# DriversBoard.net
KiCad netlist of a schematic drawn in Altium Designer
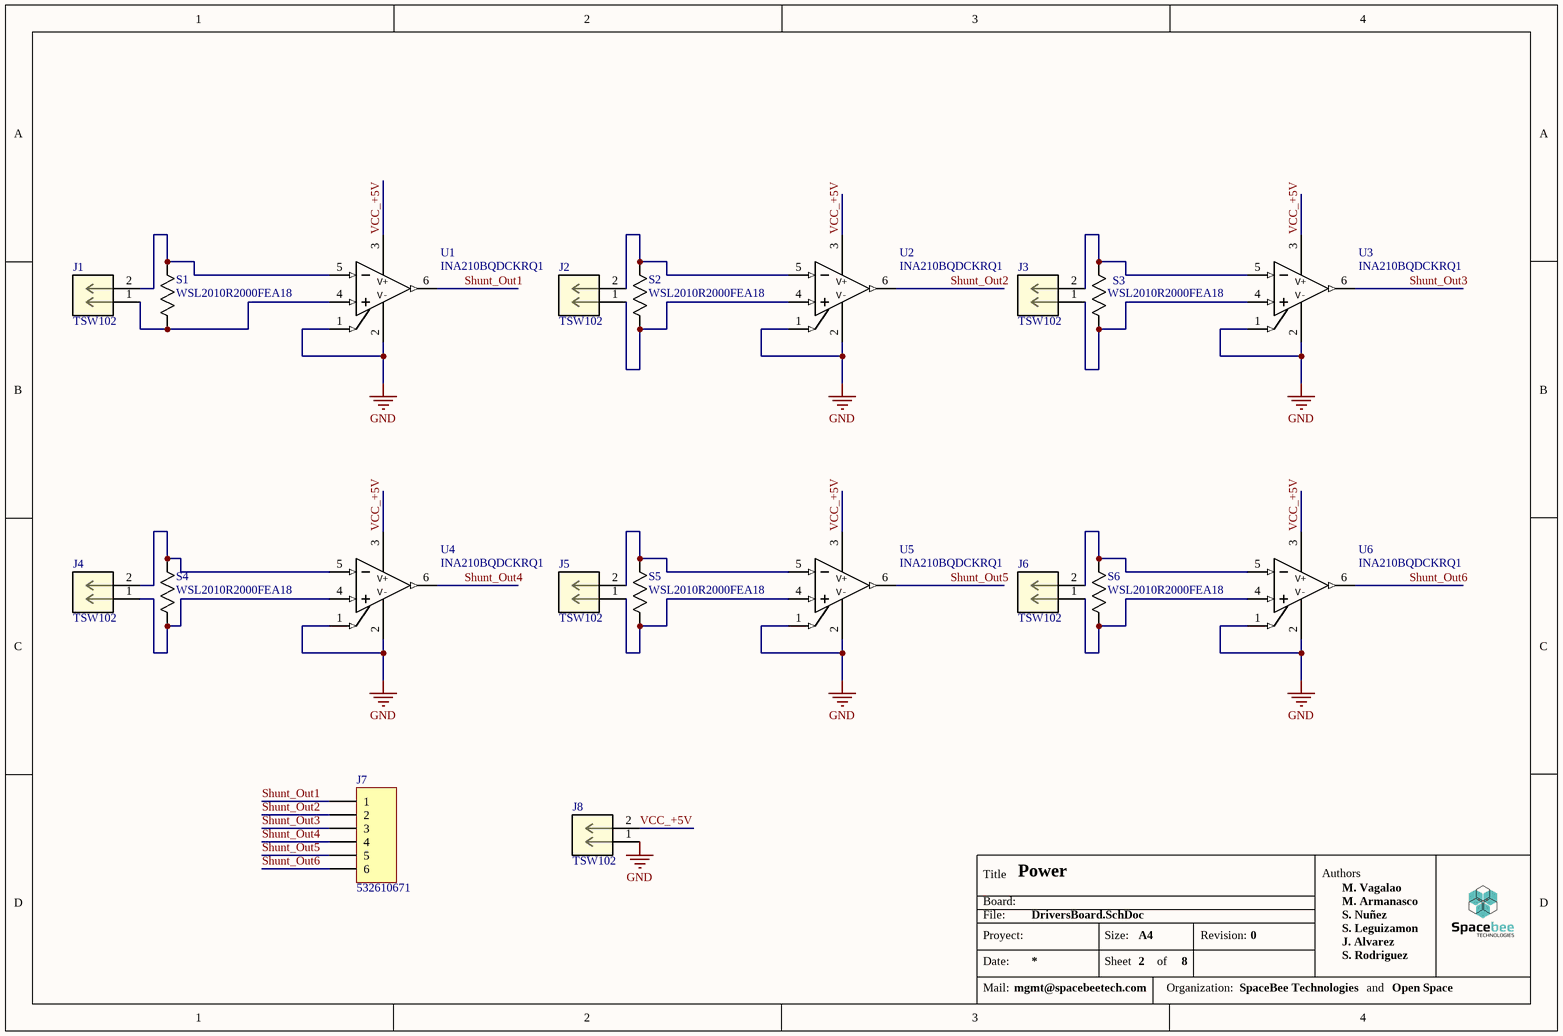
[diagram p0: DriversBoard.SchDoc]

(export (version "E")
  (design (tool "Eeschema 10.0.6"))
  (components
    (comp (ref "J1")
      (value "TSW102")
      (footprint "MOLEX_53261-0271")
      (libsource (lib "SpaceBee") (part "TSW102"))
    )
    (comp (ref "J2")
      (value "TSW102")
      (footprint "MOLEX_53261-0271")
      (libsource (lib "SpaceBee") (part "TSW102"))
    )
    (comp (ref "J3")
      (value "TSW102")
      (footprint "MOLEX_53261-0271")
      (libsource (lib "SpaceBee") (part "TSW102"))
    )
    (comp (ref "J4")
      (value "TSW102")
      (footprint "MOLEX_53261-0271")
      (libsource (lib "SpaceBee") (part "TSW102"))
    )
    (comp (ref "J5")
      (value "TSW102")
      (footprint "MOLEX_53261-0271")
      (libsource (lib "SpaceBee") (part "TSW102"))
    )
    (comp (ref "J6")
      (value "TSW102")
      (footprint "MOLEX_53261-0271")
      (libsource (lib "SpaceBee") (part "TSW102"))
    )
    (comp (ref "J7")
      (value "532610671")
      (footprint "MOLEX_532610671")
      (fields (field (name "PUBLISHER") "Altium Limited"))
      (libsource (lib "SpaceBee") (part "532610671"))
    )
    (comp (ref "J8")
      (value "TSW102")
      (footprint "MOLEX_53261-0271")
      (libsource (lib "SpaceBee") (part "TSW102"))
    )
    (comp (ref "S1")
      (value "WSL2010R2000FEA18")
      (footprint "RC2010N_VIS-L")
      (description "No Description Available")
      (fields (field (name "COPYRIGHT") "Copyright (C) 2022 Ultra Librarian. All rights reserved."))
      (libsource (lib "SpaceBee") (part "WSL2010R2000FEA18"))
    )
    (comp (ref "S2")
      (value "WSL2010R2000FEA18")
      (footprint "RC2010N_VIS-L")
      (description "No Description Available")
      (fields (field (name "COPYRIGHT") "Copyright (C) 2022 Ultra Librarian. All rights reserved."))
      (libsource (lib "SpaceBee") (part "WSL2010R2000FEA18"))
    )
    (comp (ref "S3")
      (value "WSL2010R2000FEA18")
      (footprint "RC2010N_VIS-L")
      (description "No Description Available")
      (fields (field (name "COPYRIGHT") "Copyright (C) 2022 Ultra Librarian. All rights reserved."))
      (libsource (lib "SpaceBee") (part "WSL2010R2000FEA18"))
    )
    (comp (ref "S4")
      (value "WSL2010R2000FEA18")
      (footprint "RC2010N_VIS-L")
      (description "No Description Available")
      (fields (field (name "COPYRIGHT") "Copyright (C) 2022 Ultra Librarian. All rights reserved."))
      (libsource (lib "SpaceBee") (part "WSL2010R2000FEA18"))
    )
    (comp (ref "S5")
      (value "WSL2010R2000FEA18")
      (footprint "RC2010N_VIS-L")
      (description "No Description Available")
      (fields (field (name "COPYRIGHT") "Copyright (C) 2022 Ultra Librarian. All rights reserved."))
      (libsource (lib "SpaceBee") (part "WSL2010R2000FEA18"))
    )
    (comp (ref "S6")
      (value "WSL2010R2000FEA18")
      (footprint "RC2010N_VIS-L")
      (description "No Description Available")
      (fields (field (name "COPYRIGHT") "Copyright (C) 2022 Ultra Librarian. All rights reserved."))
      (libsource (lib "SpaceBee") (part "WSL2010R2000FEA18"))
    )
    (comp (ref "U1")
      (value "INA210BQDCKRQ1")
      (footprint "INA210BQDCKRQ1")
      (fields (field (name "PART NUMBER") "296-44263-2-ND"))
      (libsource (lib "SpaceBee") (part "INA210BQDCKRQ1"))
    )
    (comp (ref "U2")
      (value "INA210BQDCKRQ1")
      (footprint "INA210BQDCKRQ1")
      (fields (field (name "PART NUMBER") "296-44263-2-ND"))
      (libsource (lib "SpaceBee") (part "INA210BQDCKRQ1"))
    )
    (comp (ref "U3")
      (value "INA210BQDCKRQ1")
      (footprint "INA210BQDCKRQ1")
      (fields (field (name "PART NUMBER") "296-44263-2-ND"))
      (libsource (lib "SpaceBee") (part "INA210BQDCKRQ1"))
    )
    (comp (ref "U4")
      (value "INA210BQDCKRQ1")
      (footprint "INA210BQDCKRQ1")
      (fields (field (name "PART NUMBER") "296-44263-2-ND"))
      (libsource (lib "SpaceBee") (part "INA210BQDCKRQ1"))
    )
    (comp (ref "U5")
      (value "INA210BQDCKRQ1")
      (footprint "INA210BQDCKRQ1")
      (fields (field (name "PART NUMBER") "296-44263-2-ND"))
      (libsource (lib "SpaceBee") (part "INA210BQDCKRQ1"))
    )
    (comp (ref "U6")
      (value "INA210BQDCKRQ1")
      (footprint "INA210BQDCKRQ1")
      (fields (field (name "PART NUMBER") "296-44263-2-ND"))
      (libsource (lib "SpaceBee") (part "INA210BQDCKRQ1"))
    )
  )
  (nets
    (net (code "1") (name "/Shunt_Out1") (class "Default")
      (node (ref "J7") (pin "1") (pinfunction "1_1") (pintype "passive"))
      (node (ref "U1") (pin "6") (pinfunction "OUT_6") (pintype "output"))
    )
    (net (code "2") (name "/Shunt_Out2") (class "Default")
      (node (ref "J7") (pin "2") (pinfunction "2_2") (pintype "passive"))
      (node (ref "U2") (pin "6") (pinfunction "OUT_6") (pintype "output"))
    )
    (net (code "3") (name "/Shunt_Out3") (class "Default")
      (node (ref "J7") (pin "3") (pinfunction "3_3") (pintype "passive"))
      (node (ref "U3") (pin "6") (pinfunction "OUT_6") (pintype "output"))
    )
    (net (code "4") (name "/Shunt_Out4") (class "Default")
      (node (ref "J7") (pin "4") (pinfunction "4_4") (pintype "passive"))
      (node (ref "U4") (pin "6") (pinfunction "OUT_6") (pintype "output"))
    )
    (net (code "5") (name "/Shunt_Out5") (class "Default")
      (node (ref "J7") (pin "5") (pinfunction "5_5") (pintype "passive"))
      (node (ref "U5") (pin "6") (pinfunction "OUT_6") (pintype "output"))
    )
    (net (code "6") (name "/Shunt_Out6") (class "Default")
      (node (ref "J7") (pin "6") (pinfunction "6_6") (pintype "passive"))
      (node (ref "U6") (pin "6") (pinfunction "OUT_6") (pintype "output"))
    )
    (net (code "7") (name "/VCC_+5V") (class "Default")
      (node (ref "J8") (pin "2") (pinfunction "2_2") (pintype "passive"))
      (node (ref "U1") (pin "3") (pinfunction "V+_3") (pintype "power_in"))
      (node (ref "U2") (pin "3") (pinfunction "V+_3") (pintype "power_in"))
      (node (ref "U3") (pin "3") (pinfunction "V+_3") (pintype "power_in"))
      (node (ref "U4") (pin "3") (pinfunction "V+_3") (pintype "power_in"))
      (node (ref "U5") (pin "3") (pinfunction "V+_3") (pintype "power_in"))
      (node (ref "U6") (pin "3") (pinfunction "V+_3") (pintype "power_in"))
    )
    (net (code "8") (name "GND") (class "Default")
      (node (ref "J8") (pin "1") (pinfunction "1_1") (pintype "passive"))
      (node (ref "U1") (pin "1") (pinfunction "REF_1") (pintype "input"))
      (node (ref "U1") (pin "2") (pinfunction "GND_2") (pintype "power_in"))
      (node (ref "U2") (pin "1") (pinfunction "REF_1") (pintype "input"))
      (node (ref "U2") (pin "2") (pinfunction "GND_2") (pintype "power_in"))
      (node (ref "U3") (pin "1") (pinfunction "REF_1") (pintype "input"))
      (node (ref "U3") (pin "2") (pinfunction "GND_2") (pintype "power_in"))
      (node (ref "U4") (pin "1") (pinfunction "REF_1") (pintype "input"))
      (node (ref "U4") (pin "2") (pinfunction "GND_2") (pintype "power_in"))
      (node (ref "U5") (pin "1") (pinfunction "REF_1") (pintype "input"))
      (node (ref "U5") (pin "2") (pinfunction "GND_2") (pintype "power_in"))
      (node (ref "U6") (pin "1") (pinfunction "REF_1") (pintype "input"))
      (node (ref "U6") (pin "2") (pinfunction "GND_2") (pintype "power_in"))
    )
    (net (code "9") (name "Net-(U1-IN+)") (class "Default")
      (node (ref "J1") (pin "1") (pinfunction "1_1") (pintype "passive"))
      (node (ref "S1") (pin "2") (pinfunction "2_2") (pintype "passive"))
      (node (ref "U1") (pin "4") (pinfunction "IN+_4") (pintype "input"))
    )
    (net (code "10") (name "Net-(U1-IN-)") (class "Default")
      (node (ref "J1") (pin "2") (pinfunction "2_2") (pintype "passive"))
      (node (ref "S1") (pin "1") (pinfunction "1_1") (pintype "passive"))
      (node (ref "U1") (pin "5") (pinfunction "IN-_5") (pintype "input"))
    )
    (net (code "11") (name "Net-(U2-IN+)") (class "Default")
      (node (ref "J2") (pin "1") (pinfunction "1_1") (pintype "passive"))
      (node (ref "S2") (pin "2") (pinfunction "2_2") (pintype "passive"))
      (node (ref "U2") (pin "4") (pinfunction "IN+_4") (pintype "input"))
    )
    (net (code "12") (name "Net-(U2-IN-)") (class "Default")
      (node (ref "J2") (pin "2") (pinfunction "2_2") (pintype "passive"))
      (node (ref "S2") (pin "1") (pinfunction "1_1") (pintype "passive"))
      (node (ref "U2") (pin "5") (pinfunction "IN-_5") (pintype "input"))
    )
    (net (code "13") (name "Net-(U3-IN+)") (class "Default")
      (node (ref "J3") (pin "1") (pinfunction "1_1") (pintype "passive"))
      (node (ref "S3") (pin "2") (pinfunction "2_2") (pintype "passive"))
      (node (ref "U3") (pin "4") (pinfunction "IN+_4") (pintype "input"))
    )
    (net (code "14") (name "Net-(U3-IN-)") (class "Default")
      (node (ref "J3") (pin "2") (pinfunction "2_2") (pintype "passive"))
      (node (ref "S3") (pin "1") (pinfunction "1_1") (pintype "passive"))
      (node (ref "U3") (pin "5") (pinfunction "IN-_5") (pintype "input"))
    )
    (net (code "15") (name "Net-(U4-IN+)") (class "Default")
      (node (ref "J4") (pin "1") (pinfunction "1_1") (pintype "passive"))
      (node (ref "S4") (pin "2") (pinfunction "2_2") (pintype "passive"))
      (node (ref "U4") (pin "4") (pinfunction "IN+_4") (pintype "input"))
    )
    (net (code "16") (name "Net-(U4-IN-)") (class "Default")
      (node (ref "J4") (pin "2") (pinfunction "2_2") (pintype "passive"))
      (node (ref "S4") (pin "1") (pinfunction "1_1") (pintype "passive"))
      (node (ref "U4") (pin "5") (pinfunction "IN-_5") (pintype "input"))
    )
    (net (code "17") (name "Net-(U5-IN+)") (class "Default")
      (node (ref "J5") (pin "1") (pinfunction "1_1") (pintype "passive"))
      (node (ref "S5") (pin "2") (pinfunction "2_2") (pintype "passive"))
      (node (ref "U5") (pin "4") (pinfunction "IN+_4") (pintype "input"))
    )
    (net (code "18") (name "Net-(U5-IN-)") (class "Default")
      (node (ref "J5") (pin "2") (pinfunction "2_2") (pintype "passive"))
      (node (ref "S5") (pin "1") (pinfunction "1_1") (pintype "passive"))
      (node (ref "U5") (pin "5") (pinfunction "IN-_5") (pintype "input"))
    )
    (net (code "19") (name "Net-(U6-IN+)") (class "Default")
      (node (ref "J6") (pin "1") (pinfunction "1_1") (pintype "passive"))
      (node (ref "S6") (pin "2") (pinfunction "2_2") (pintype "passive"))
      (node (ref "U6") (pin "4") (pinfunction "IN+_4") (pintype "input"))
    )
    (net (code "20") (name "Net-(U6-IN-)") (class "Default")
      (node (ref "J6") (pin "2") (pinfunction "2_2") (pintype "passive"))
      (node (ref "S6") (pin "1") (pinfunction "1_1") (pintype "passive"))
      (node (ref "U6") (pin "5") (pinfunction "IN-_5") (pintype "input"))
    )
  )
)
